# Stepper5_bakcup.net
KiCad netlist of a schematic drawn in EAGLE
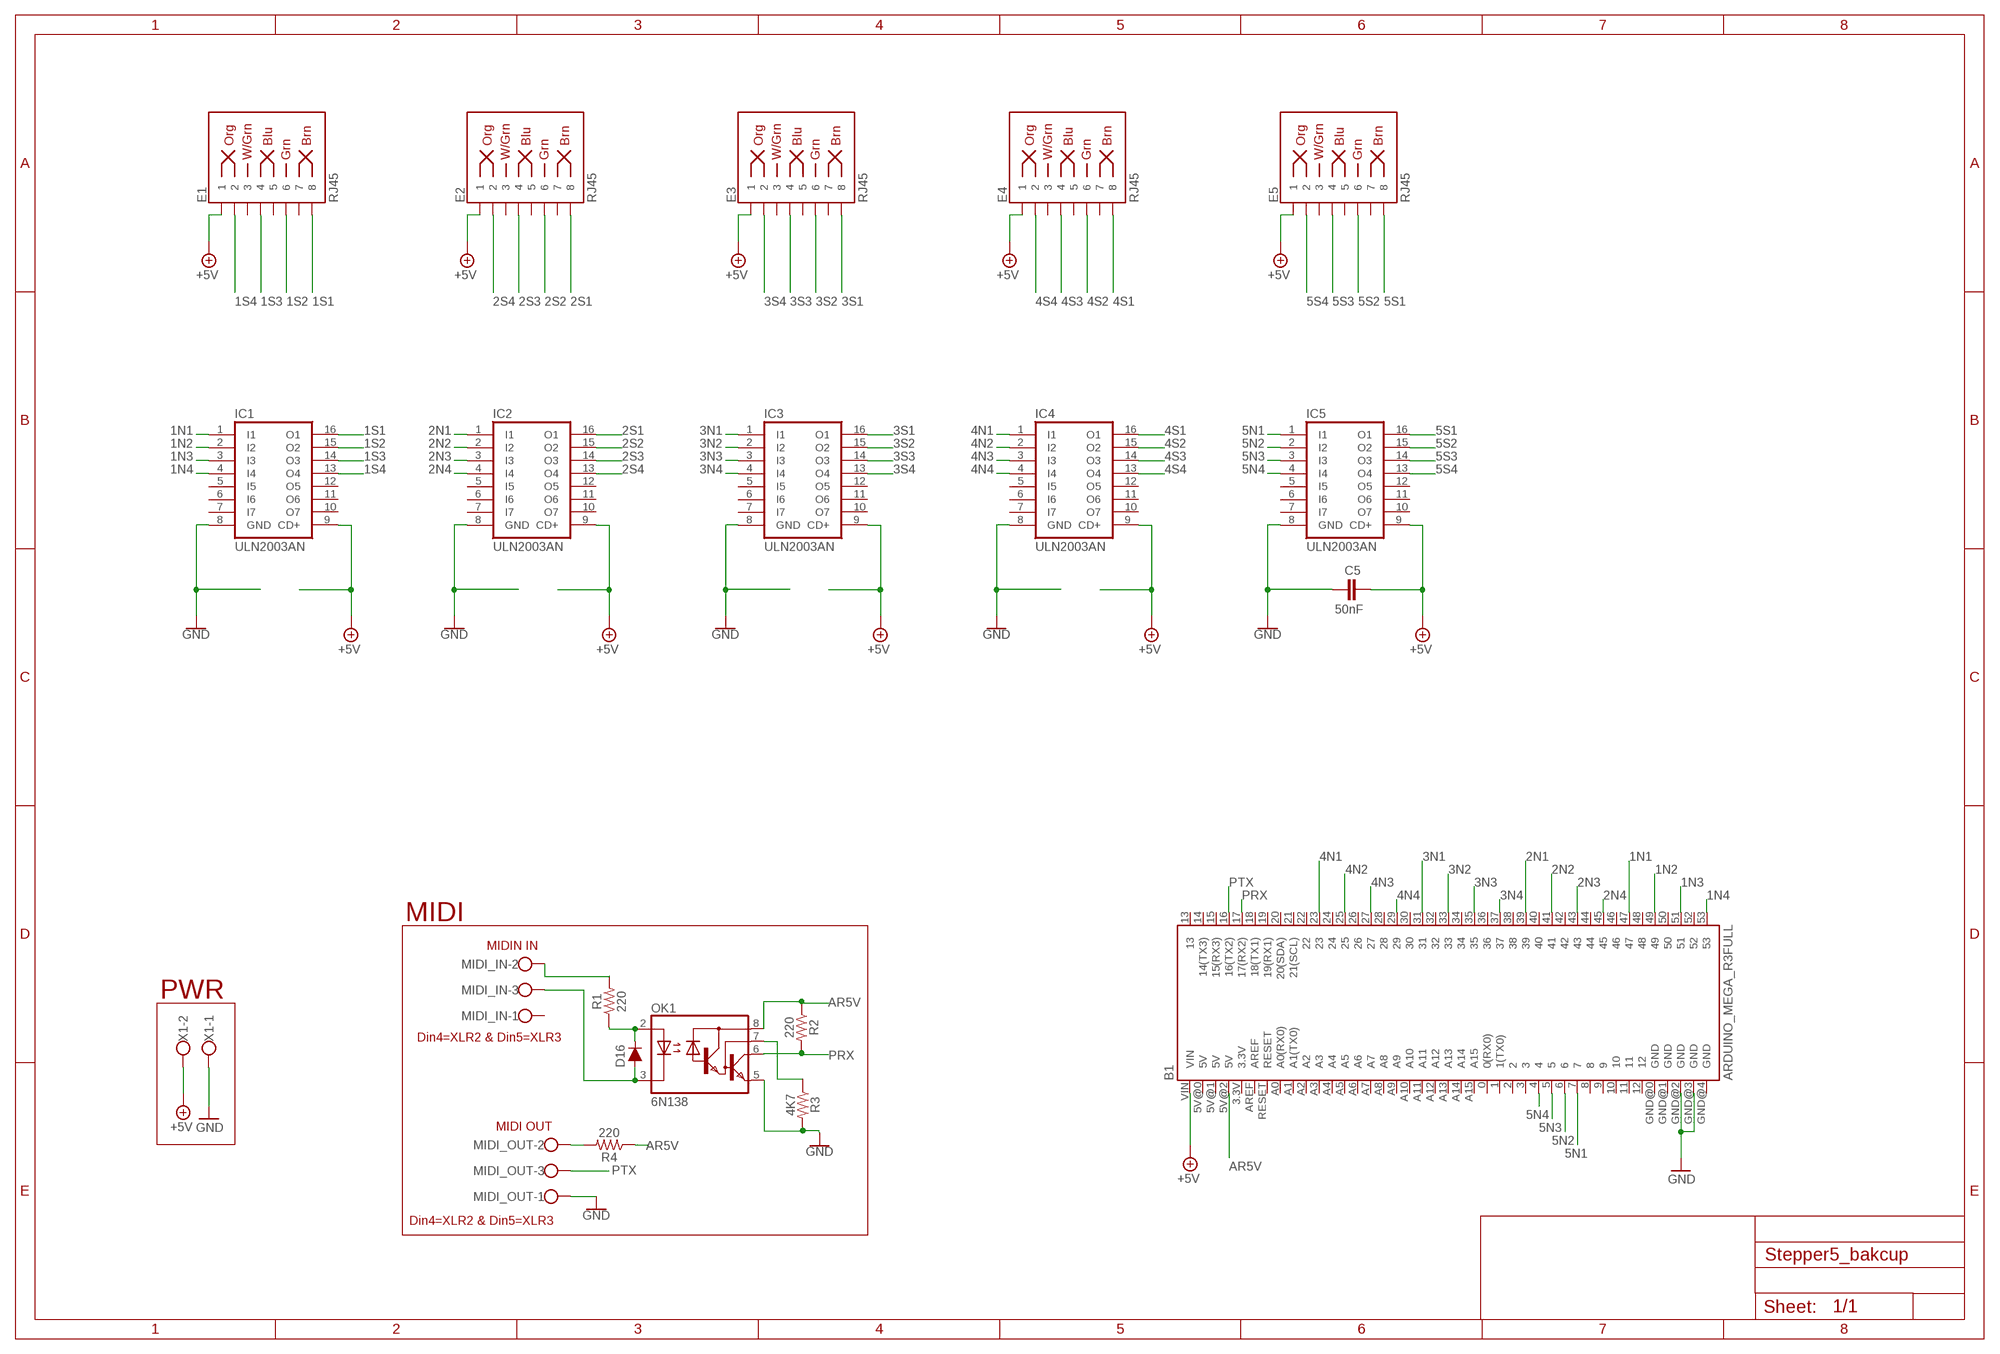
[diagram p0: schematic, sheet 1]

(export (version "E")
  (design (tool "Eeschema 10.0.6"))
  (components
    (comp (ref "B1")
      (value "ARDUINO_MEGA_R3FULL")
      (footprint "eagle-import:ARDUINO_MEGA")
      (libsource (lib "eagle-import") (part "ARDUINO_MEGA_R3FULL"))
    )
    (comp (ref "C5")
      (value "50nF")
      (footprint "eagle-import:C5B2.5")
      (libsource (lib "eagle-import") (part "C5/2.5"))
    )
    (comp (ref "D16")
      (value "200mA/100V/1V")
      (footprint "eagle-import:DIODE-1N4148")
      (libsource (lib "eagle-import") (part "DIODE-1N4148"))
    )
    (comp (ref "E1")
      (value "RJ45")
      (footprint "eagle-import:RJ45-8")
      (libsource (lib "eagle-import") (part "RJ45-8"))
    )
    (comp (ref "E2")
      (value "RJ45")
      (footprint "eagle-import:RJ45-8")
      (libsource (lib "eagle-import") (part "RJ45-8"))
    )
    (comp (ref "E3")
      (value "RJ45")
      (footprint "eagle-import:RJ45-8")
      (libsource (lib "eagle-import") (part "RJ45-8"))
    )
    (comp (ref "E4")
      (value "RJ45")
      (footprint "eagle-import:RJ45-8")
      (libsource (lib "eagle-import") (part "RJ45-8"))
    )
    (comp (ref "E5")
      (value "RJ45")
      (footprint "eagle-import:RJ45-8")
      (libsource (lib "eagle-import") (part "RJ45-8"))
    )
    (comp (ref "IC1")
      (value "ULN2003AN")
      (footprint "eagle-import:DIL16")
      (libsource (lib "eagle-import") (part "ULN2003AN"))
    )
    (comp (ref "IC2")
      (value "ULN2003AN")
      (footprint "eagle-import:DIL16")
      (libsource (lib "eagle-import") (part "ULN2003AN"))
    )
    (comp (ref "IC3")
      (value "ULN2003AN")
      (footprint "eagle-import:DIL16")
      (libsource (lib "eagle-import") (part "ULN2003AN"))
    )
    (comp (ref "IC4")
      (value "ULN2003AN")
      (footprint "eagle-import:DIL16")
      (libsource (lib "eagle-import") (part "ULN2003AN"))
    )
    (comp (ref "IC5")
      (value "ULN2003AN")
      (footprint "eagle-import:DIL16")
      (libsource (lib "eagle-import") (part "ULN2003AN"))
    )
    (comp (ref "MIDI_IN")
      (value "W237-103")
      (footprint "eagle-import:W237-103")
      (fields (field (name "MPN") "237-103"))
      (libsource (lib "eagle-import") (part "W237-103"))
    )
    (comp (ref "MIDI_OUT")
      (value "W237-103")
      (footprint "eagle-import:W237-103")
      (fields (field (name "MPN") "237-103"))
      (libsource (lib "eagle-import") (part "W237-103"))
    )
    (comp (ref "OK1")
      (value "6N138")
      (footprint "eagle-import:DIL08")
      (fields (field (name "MF") "VISHAY/TELEFUNKEN"))
      (libsource (lib "eagle-import") (part "6N138"))
    )
    (comp (ref "R1")
      (value "220")
      (footprint "eagle-import:AXIAL-0.3")
      (libsource (lib "eagle-import") (part "1KOHM-HORIZ-1/4W-5%"))
    )
    (comp (ref "R2")
      (value "220")
      (footprint "eagle-import:AXIAL-0.3")
      (libsource (lib "eagle-import") (part "1KOHM-HORIZ-1/4W-5%"))
    )
    (comp (ref "R3")
      (value "4K7")
      (footprint "eagle-import:AXIAL-0.3")
      (libsource (lib "eagle-import") (part "1KOHM-HORIZ-1/4W-5%"))
    )
    (comp (ref "R4")
      (value "220")
      (footprint "eagle-import:AXIAL-0.3")
      (libsource (lib "eagle-import") (part "1KOHM-HORIZ-1/4W-5%"))
    )
    (comp (ref "X1")
      (value "W237-102")
      (footprint "eagle-import:W237-102")
      (fields (field (name "MPN") "237-102"))
      (libsource (lib "eagle-import") (part "W237-102"))
    )
  )
  (nets
    (net (code "1") (name "+5V") (class "Default")
      (node (ref "B1") (pin "VIN") (pinfunction "VIN_VIN") (pintype "bidirectional"))
      (node (ref "C5") (pin "2") (pinfunction "2_2") (pintype "passive"))
      (node (ref "E1") (pin "1") (pinfunction "1_1") (pintype "bidirectional"))
      (node (ref "E2") (pin "1") (pinfunction "1_1") (pintype "bidirectional"))
      (node (ref "E3") (pin "1") (pinfunction "1_1") (pintype "bidirectional"))
      (node (ref "E4") (pin "1") (pinfunction "1_1") (pintype "bidirectional"))
      (node (ref "E5") (pin "1") (pinfunction "1_1") (pintype "bidirectional"))
      (node (ref "IC1") (pin "9") (pinfunction "CD+_9") (pintype "passive"))
      (node (ref "IC2") (pin "9") (pinfunction "CD+_9") (pintype "passive"))
      (node (ref "IC3") (pin "9") (pinfunction "CD+_9") (pintype "passive"))
      (node (ref "IC4") (pin "9") (pinfunction "CD+_9") (pintype "passive"))
      (node (ref "IC5") (pin "9") (pinfunction "CD+_9") (pintype "passive"))
      (node (ref "X1") (pin "2") (pinfunction "KL_2") (pintype "passive"))
    )
    (net (code "2") (name "/1N1") (class "Default")
      (node (ref "B1") (pin "47") (pinfunction "47_47") (pintype "bidirectional"))
      (node (ref "IC1") (pin "1") (pinfunction "I1_1") (pintype "input"))
    )
    (net (code "3") (name "/1N2") (class "Default")
      (node (ref "B1") (pin "49") (pinfunction "49_49") (pintype "bidirectional"))
      (node (ref "IC1") (pin "2") (pinfunction "I2_2") (pintype "input"))
    )
    (net (code "4") (name "/1N3") (class "Default")
      (node (ref "B1") (pin "51") (pinfunction "51_51") (pintype "bidirectional"))
      (node (ref "IC1") (pin "3") (pinfunction "I3_3") (pintype "input"))
    )
    (net (code "5") (name "/1N4") (class "Default")
      (node (ref "B1") (pin "53") (pinfunction "53_53") (pintype "bidirectional"))
      (node (ref "IC1") (pin "4") (pinfunction "I4_4") (pintype "input"))
    )
    (net (code "6") (name "/1S1") (class "Default")
      (node (ref "E1") (pin "8") (pinfunction "8_8") (pintype "bidirectional"))
      (node (ref "IC1") (pin "16") (pinfunction "O1_16") (pintype "open_collector"))
    )
    (net (code "7") (name "/1S2") (class "Default")
      (node (ref "E1") (pin "6") (pinfunction "6_6") (pintype "bidirectional"))
      (node (ref "IC1") (pin "15") (pinfunction "O2_15") (pintype "open_collector"))
    )
    (net (code "8") (name "/1S3") (class "Default")
      (node (ref "E1") (pin "4") (pinfunction "4_4") (pintype "bidirectional"))
      (node (ref "IC1") (pin "14") (pinfunction "O3_14") (pintype "open_collector"))
    )
    (net (code "9") (name "/1S4") (class "Default")
      (node (ref "E1") (pin "2") (pinfunction "2_2") (pintype "bidirectional"))
      (node (ref "IC1") (pin "13") (pinfunction "O4_13") (pintype "open_collector"))
    )
    (net (code "10") (name "/2N1") (class "Default")
      (node (ref "B1") (pin "39") (pinfunction "39_39") (pintype "bidirectional"))
      (node (ref "IC2") (pin "1") (pinfunction "I1_1") (pintype "input"))
    )
    (net (code "11") (name "/2N2") (class "Default")
      (node (ref "B1") (pin "41") (pinfunction "41_41") (pintype "bidirectional"))
      (node (ref "IC2") (pin "2") (pinfunction "I2_2") (pintype "input"))
    )
    (net (code "12") (name "/2N3") (class "Default")
      (node (ref "B1") (pin "43") (pinfunction "43_43") (pintype "bidirectional"))
      (node (ref "IC2") (pin "3") (pinfunction "I3_3") (pintype "input"))
    )
    (net (code "13") (name "/2N4") (class "Default")
      (node (ref "B1") (pin "45") (pinfunction "45_45") (pintype "bidirectional"))
      (node (ref "IC2") (pin "4") (pinfunction "I4_4") (pintype "input"))
    )
    (net (code "14") (name "/2S1") (class "Default")
      (node (ref "E2") (pin "8") (pinfunction "8_8") (pintype "bidirectional"))
      (node (ref "IC2") (pin "16") (pinfunction "O1_16") (pintype "open_collector"))
    )
    (net (code "15") (name "/2S2") (class "Default")
      (node (ref "E2") (pin "6") (pinfunction "6_6") (pintype "bidirectional"))
      (node (ref "IC2") (pin "15") (pinfunction "O2_15") (pintype "open_collector"))
    )
    (net (code "16") (name "/2S3") (class "Default")
      (node (ref "E2") (pin "4") (pinfunction "4_4") (pintype "bidirectional"))
      (node (ref "IC2") (pin "14") (pinfunction "O3_14") (pintype "open_collector"))
    )
    (net (code "17") (name "/2S4") (class "Default")
      (node (ref "E2") (pin "2") (pinfunction "2_2") (pintype "bidirectional"))
      (node (ref "IC2") (pin "13") (pinfunction "O4_13") (pintype "open_collector"))
    )
    (net (code "18") (name "/3N1") (class "Default")
      (node (ref "B1") (pin "31") (pinfunction "31_31") (pintype "bidirectional"))
      (node (ref "IC3") (pin "1") (pinfunction "I1_1") (pintype "input"))
    )
    (net (code "19") (name "/3N2") (class "Default")
      (node (ref "B1") (pin "33") (pinfunction "33_33") (pintype "bidirectional"))
      (node (ref "IC3") (pin "2") (pinfunction "I2_2") (pintype "input"))
    )
    (net (code "20") (name "/3N3") (class "Default")
      (node (ref "B1") (pin "35") (pinfunction "35_35") (pintype "bidirectional"))
      (node (ref "IC3") (pin "3") (pinfunction "I3_3") (pintype "input"))
    )
    (net (code "21") (name "/3N4") (class "Default")
      (node (ref "B1") (pin "37") (pinfunction "37_37") (pintype "bidirectional"))
      (node (ref "IC3") (pin "4") (pinfunction "I4_4") (pintype "input"))
    )
    (net (code "22") (name "/3S1") (class "Default")
      (node (ref "E3") (pin "8") (pinfunction "8_8") (pintype "bidirectional"))
      (node (ref "IC3") (pin "16") (pinfunction "O1_16") (pintype "open_collector"))
    )
    (net (code "23") (name "/3S2") (class "Default")
      (node (ref "E3") (pin "6") (pinfunction "6_6") (pintype "bidirectional"))
      (node (ref "IC3") (pin "15") (pinfunction "O2_15") (pintype "open_collector"))
    )
    (net (code "24") (name "/3S3") (class "Default")
      (node (ref "E3") (pin "4") (pinfunction "4_4") (pintype "bidirectional"))
      (node (ref "IC3") (pin "14") (pinfunction "O3_14") (pintype "open_collector"))
    )
    (net (code "25") (name "/3S4") (class "Default")
      (node (ref "E3") (pin "2") (pinfunction "2_2") (pintype "bidirectional"))
      (node (ref "IC3") (pin "13") (pinfunction "O4_13") (pintype "open_collector"))
    )
    (net (code "26") (name "/4N1") (class "Default")
      (node (ref "B1") (pin "23") (pinfunction "23_23") (pintype "bidirectional"))
      (node (ref "IC4") (pin "1") (pinfunction "I1_1") (pintype "input"))
    )
    (net (code "27") (name "/4N2") (class "Default")
      (node (ref "B1") (pin "25") (pinfunction "25_25") (pintype "bidirectional"))
      (node (ref "IC4") (pin "2") (pinfunction "I2_2") (pintype "input"))
    )
    (net (code "28") (name "/4N3") (class "Default")
      (node (ref "B1") (pin "27") (pinfunction "27_27") (pintype "bidirectional"))
      (node (ref "IC4") (pin "3") (pinfunction "I3_3") (pintype "input"))
    )
    (net (code "29") (name "/4N4") (class "Default")
      (node (ref "B1") (pin "29") (pinfunction "29_29") (pintype "bidirectional"))
      (node (ref "IC4") (pin "4") (pinfunction "I4_4") (pintype "input"))
    )
    (net (code "30") (name "/4S1") (class "Default")
      (node (ref "E4") (pin "8") (pinfunction "8_8") (pintype "bidirectional"))
      (node (ref "IC4") (pin "16") (pinfunction "O1_16") (pintype "open_collector"))
    )
    (net (code "31") (name "/4S2") (class "Default")
      (node (ref "E4") (pin "6") (pinfunction "6_6") (pintype "bidirectional"))
      (node (ref "IC4") (pin "15") (pinfunction "O2_15") (pintype "open_collector"))
    )
    (net (code "32") (name "/4S3") (class "Default")
      (node (ref "E4") (pin "4") (pinfunction "4_4") (pintype "bidirectional"))
      (node (ref "IC4") (pin "14") (pinfunction "O3_14") (pintype "open_collector"))
    )
    (net (code "33") (name "/4S4") (class "Default")
      (node (ref "E4") (pin "2") (pinfunction "2_2") (pintype "bidirectional"))
      (node (ref "IC4") (pin "13") (pinfunction "O4_13") (pintype "open_collector"))
    )
    (net (code "34") (name "/5N1") (class "Default")
      (node (ref "B1") (pin "7") (pinfunction "7_7") (pintype "bidirectional"))
      (node (ref "IC5") (pin "1") (pinfunction "I1_1") (pintype "input"))
    )
    (net (code "35") (name "/5N2") (class "Default")
      (node (ref "B1") (pin "6") (pinfunction "6_6") (pintype "bidirectional"))
      (node (ref "IC5") (pin "2") (pinfunction "I2_2") (pintype "input"))
    )
    (net (code "36") (name "/5N3") (class "Default")
      (node (ref "B1") (pin "5") (pinfunction "5_5") (pintype "bidirectional"))
      (node (ref "IC5") (pin "3") (pinfunction "I3_3") (pintype "input"))
    )
    (net (code "37") (name "/5N4") (class "Default")
      (node (ref "B1") (pin "4") (pinfunction "4_4") (pintype "bidirectional"))
      (node (ref "IC5") (pin "4") (pinfunction "I4_4") (pintype "input"))
    )
    (net (code "38") (name "/5S1") (class "Default")
      (node (ref "E5") (pin "8") (pinfunction "8_8") (pintype "bidirectional"))
      (node (ref "IC5") (pin "16") (pinfunction "O1_16") (pintype "open_collector"))
    )
    (net (code "39") (name "/5S2") (class "Default")
      (node (ref "E5") (pin "6") (pinfunction "6_6") (pintype "bidirectional"))
      (node (ref "IC5") (pin "15") (pinfunction "O2_15") (pintype "open_collector"))
    )
    (net (code "40") (name "/5S3") (class "Default")
      (node (ref "E5") (pin "4") (pinfunction "4_4") (pintype "bidirectional"))
      (node (ref "IC5") (pin "14") (pinfunction "O3_14") (pintype "open_collector"))
    )
    (net (code "41") (name "/5S4") (class "Default")
      (node (ref "E5") (pin "2") (pinfunction "2_2") (pintype "bidirectional"))
      (node (ref "IC5") (pin "13") (pinfunction "O4_13") (pintype "open_collector"))
    )
    (net (code "42") (name "/AR5V") (class "Default")
      (node (ref "B1") (pin "5V@2") (pinfunction "5V_5V@2") (pintype "bidirectional"))
      (node (ref "OK1") (pin "8") (pinfunction "VCC_8") (pintype "passive"))
      (node (ref "R2") (pin "P$1") (pinfunction "1_P$1") (pintype "passive"))
      (node (ref "R4") (pin "P$1") (pinfunction "1_P$1") (pintype "passive"))
    )
    (net (code "43") (name "/PRX") (class "Default")
      (node (ref "B1") (pin "17") (pinfunction "17(RX2)_17") (pintype "bidirectional"))
      (node (ref "OK1") (pin "6") (pinfunction "VO_6") (pintype "passive"))
      (node (ref "R2") (pin "P$2") (pinfunction "2_P$2") (pintype "passive"))
    )
    (net (code "44") (name "/PTX") (class "Default")
      (node (ref "B1") (pin "16") (pinfunction "16(TX2)_16") (pintype "bidirectional"))
      (node (ref "MIDI_OUT") (pin "3") (pinfunction "KL_3") (pintype "passive"))
    )
    (net (code "45") (name "GND") (class "Default")
      (node (ref "B1") (pin "GND@2") (pinfunction "GND_GND@2") (pintype "bidirectional"))
      (node (ref "B1") (pin "GND@3") (pinfunction "GND_GND@3") (pintype "bidirectional"))
      (node (ref "C5") (pin "1") (pinfunction "1_1") (pintype "passive"))
      (node (ref "IC1") (pin "8") (pinfunction "GND_8") (pintype "power_in"))
      (node (ref "IC2") (pin "8") (pinfunction "GND_8") (pintype "power_in"))
      (node (ref "IC3") (pin "8") (pinfunction "GND_8") (pintype "power_in"))
      (node (ref "IC4") (pin "8") (pinfunction "GND_8") (pintype "power_in"))
      (node (ref "IC5") (pin "8") (pinfunction "GND_8") (pintype "power_in"))
      (node (ref "MIDI_OUT") (pin "1") (pinfunction "KL_1") (pintype "passive"))
      (node (ref "OK1") (pin "5") (pinfunction "GND_5") (pintype "passive"))
      (node (ref "R3") (pin "P$2") (pinfunction "2_P$2") (pintype "passive"))
      (node (ref "X1") (pin "1") (pinfunction "KL_1") (pintype "passive"))
    )
    (net (code "46") (name "Net-(MIDI_INB-KL)") (class "Default")
      (node (ref "MIDI_IN") (pin "2") (pinfunction "KL_2") (pintype "passive"))
      (node (ref "R1") (pin "P$2") (pinfunction "2_P$2") (pintype "passive"))
    )
    (net (code "47") (name "Net-(MIDI_INC-KL)") (class "Default")
      (node (ref "D16") (pin "A") (pinfunction "A_A") (pintype "passive"))
      (node (ref "MIDI_IN") (pin "3") (pinfunction "KL_3") (pintype "passive"))
      (node (ref "OK1") (pin "3") (pinfunction "C_3") (pintype "passive"))
    )
    (net (code "48") (name "Net-(MIDI_OUTB-KL)") (class "Default")
      (node (ref "MIDI_OUT") (pin "2") (pinfunction "KL_2") (pintype "passive"))
      (node (ref "R4") (pin "P$2") (pinfunction "2_P$2") (pintype "passive"))
    )
    (net (code "49") (name "Net-(OK1-A)") (class "Default")
      (node (ref "D16") (pin "C") (pinfunction "C_C") (pintype "passive"))
      (node (ref "OK1") (pin "2") (pinfunction "A_2") (pintype "passive"))
      (node (ref "R1") (pin "P$1") (pinfunction "1_P$1") (pintype "passive"))
    )
    (net (code "50") (name "Net-(OK1-VB)") (class "Default")
      (node (ref "OK1") (pin "7") (pinfunction "VB_7") (pintype "passive"))
      (node (ref "R3") (pin "P$1") (pinfunction "1_P$1") (pintype "passive"))
    )
    (net (code "51") (name "unconnected-(B1-0(RX0)-Pad0)") (class "Default")
      (node (ref "B1") (pin "0") (pinfunction "0(RX0)_0") (pintype "bidirectional"))
    )
    (net (code "52") (name "unconnected-(B1-1(TX0)-Pad1)") (class "Default")
      (node (ref "B1") (pin "1") (pinfunction "1(TX0)_1") (pintype "bidirectional"))
    )
    (net (code "53") (name "unconnected-(B1-5V-Pad5V@0)") (class "Default")
      (node (ref "B1") (pin "5V@0") (pinfunction "5V_5V@0") (pintype "bidirectional"))
    )
    (net (code "54") (name "unconnected-(B1-5V-Pad5V@1)") (class "Default")
      (node (ref "B1") (pin "5V@1") (pinfunction "5V_5V@1") (pintype "bidirectional"))
    )
    (net (code "55") (name "unconnected-(B1-14(TX3)-Pad14)") (class "Default")
      (node (ref "B1") (pin "14") (pinfunction "14(TX3)_14") (pintype "bidirectional"))
    )
    (net (code "56") (name "unconnected-(B1-15(RX3)-Pad15)") (class "Default")
      (node (ref "B1") (pin "15") (pinfunction "15(RX3)_15") (pintype "bidirectional"))
    )
    (net (code "57") (name "unconnected-(B1-18(TX1)-Pad18)") (class "Default")
      (node (ref "B1") (pin "18") (pinfunction "18(TX1)_18") (pintype "bidirectional"))
    )
    (net (code "58") (name "unconnected-(B1-19(RX1)-Pad19)") (class "Default")
      (node (ref "B1") (pin "19") (pinfunction "19(RX1)_19") (pintype "bidirectional"))
    )
    (net (code "59") (name "unconnected-(B1-20(SDA)-Pad20)") (class "Default")
      (node (ref "B1") (pin "20") (pinfunction "20(SDA)_20") (pintype "bidirectional"))
    )
    (net (code "60") (name "unconnected-(B1-21(SCL)-Pad21)") (class "Default")
      (node (ref "B1") (pin "21") (pinfunction "21(SCL)_21") (pintype "bidirectional"))
    )
    (net (code "61") (name "unconnected-(B1-A0(RX0)-PadA0)") (class "Default")
      (node (ref "B1") (pin "A0") (pinfunction "A0(RX0)_A0") (pintype "bidirectional"))
    )
    (net (code "62") (name "unconnected-(B1-A1(TX0)-PadA1)") (class "Default")
      (node (ref "B1") (pin "A1") (pinfunction "A1(TX0)_A1") (pintype "bidirectional"))
    )
    (net (code "63") (name "unconnected-(B1-GND-PadGND@0)") (class "Default")
      (node (ref "B1") (pin "GND@0") (pinfunction "GND_GND@0") (pintype "bidirectional"))
    )
    (net (code "64") (name "unconnected-(B1-GND-PadGND@1)") (class "Default")
      (node (ref "B1") (pin "GND@1") (pinfunction "GND_GND@1") (pintype "bidirectional"))
    )
    (net (code "65") (name "unconnected-(B1-GND-PadGND@4)") (class "Default")
      (node (ref "B1") (pin "GND@4") (pinfunction "GND_GND@4") (pintype "bidirectional"))
    )
    (net (code "66") (name "unconnected-(B1-Pad2)") (class "Default")
      (node (ref "B1") (pin "2") (pinfunction "2_2") (pintype "bidirectional"))
    )
    (net (code "67") (name "unconnected-(B1-Pad3)") (class "Default")
      (node (ref "B1") (pin "3") (pinfunction "3_3") (pintype "bidirectional"))
    )
    (net (code "68") (name "unconnected-(B1-Pad3.3V)") (class "Default")
      (node (ref "B1") (pin "3.3V") (pinfunction "3.3V_3.3V") (pintype "bidirectional"))
    )
    (net (code "69") (name "unconnected-(B1-Pad8)") (class "Default")
      (node (ref "B1") (pin "8") (pinfunction "8_8") (pintype "bidirectional"))
    )
    (net (code "70") (name "unconnected-(B1-Pad9)") (class "Default")
      (node (ref "B1") (pin "9") (pinfunction "9_9") (pintype "bidirectional"))
    )
    (net (code "71") (name "unconnected-(B1-Pad10)") (class "Default")
      (node (ref "B1") (pin "10") (pinfunction "10_10") (pintype "bidirectional"))
    )
    (net (code "72") (name "unconnected-(B1-Pad11)") (class "Default")
      (node (ref "B1") (pin "11") (pinfunction "11_11") (pintype "bidirectional"))
    )
    (net (code "73") (name "unconnected-(B1-Pad12)") (class "Default")
      (node (ref "B1") (pin "12") (pinfunction "12_12") (pintype "bidirectional"))
    )
    (net (code "74") (name "unconnected-(B1-Pad13)") (class "Default")
      (node (ref "B1") (pin "13") (pinfunction "13_13") (pintype "bidirectional"))
    )
    (net (code "75") (name "unconnected-(B1-Pad22)") (class "Default")
      (node (ref "B1") (pin "22") (pinfunction "22_22") (pintype "bidirectional"))
    )
    (net (code "76") (name "unconnected-(B1-Pad24)") (class "Default")
      (node (ref "B1") (pin "24") (pinfunction "24_24") (pintype "bidirectional"))
    )
    (net (code "77") (name "unconnected-(B1-Pad26)") (class "Default")
      (node (ref "B1") (pin "26") (pinfunction "26_26") (pintype "bidirectional"))
    )
    (net (code "78") (name "unconnected-(B1-Pad28)") (class "Default")
      (node (ref "B1") (pin "28") (pinfunction "28_28") (pintype "bidirectional"))
    )
    (net (code "79") (name "unconnected-(B1-Pad30)") (class "Default")
      (node (ref "B1") (pin "30") (pinfunction "30_30") (pintype "bidirectional"))
    )
    (net (code "80") (name "unconnected-(B1-Pad32)") (class "Default")
      (node (ref "B1") (pin "32") (pinfunction "32_32") (pintype "bidirectional"))
    )
    (net (code "81") (name "unconnected-(B1-Pad34)") (class "Default")
      (node (ref "B1") (pin "34") (pinfunction "34_34") (pintype "bidirectional"))
    )
    (net (code "82") (name "unconnected-(B1-Pad36)") (class "Default")
      (node (ref "B1") (pin "36") (pinfunction "36_36") (pintype "bidirectional"))
    )
    (net (code "83") (name "unconnected-(B1-Pad38)") (class "Default")
      (node (ref "B1") (pin "38") (pinfunction "38_38") (pintype "bidirectional"))
    )
    (net (code "84") (name "unconnected-(B1-Pad40)") (class "Default")
      (node (ref "B1") (pin "40") (pinfunction "40_40") (pintype "bidirectional"))
    )
    (net (code "85") (name "unconnected-(B1-Pad42)") (class "Default")
      (node (ref "B1") (pin "42") (pinfunction "42_42") (pintype "bidirectional"))
    )
    (net (code "86") (name "unconnected-(B1-Pad44)") (class "Default")
      (node (ref "B1") (pin "44") (pinfunction "44_44") (pintype "bidirectional"))
    )
    (net (code "87") (name "unconnected-(B1-Pad46)") (class "Default")
      (node (ref "B1") (pin "46") (pinfunction "46_46") (pintype "bidirectional"))
    )
    (net (code "88") (name "unconnected-(B1-Pad48)") (class "Default")
      (node (ref "B1") (pin "48") (pinfunction "48_48") (pintype "bidirectional"))
    )
    (net (code "89") (name "unconnected-(B1-Pad50)") (class "Default")
      (node (ref "B1") (pin "50") (pinfunction "50_50") (pintype "bidirectional"))
    )
    (net (code "90") (name "unconnected-(B1-Pad52)") (class "Default")
      (node (ref "B1") (pin "52") (pinfunction "52_52") (pintype "bidirectional"))
    )
    (net (code "91") (name "unconnected-(B1-PadA2)") (class "Default")
      (node (ref "B1") (pin "A2") (pinfunction "A2_A2") (pintype "bidirectional"))
    )
    (net (code "92") (name "unconnected-(B1-PadA3)") (class "Default")
      (node (ref "B1") (pin "A3") (pinfunction "A3_A3") (pintype "bidirectional"))
    )
    (net (code "93") (name "unconnected-(B1-PadA4)") (class "Default")
      (node (ref "B1") (pin "A4") (pinfunction "A4_A4") (pintype "bidirectional"))
    )
    (net (code "94") (name "unconnected-(B1-PadA5)") (class "Default")
      (node (ref "B1") (pin "A5") (pinfunction "A5_A5") (pintype "bidirectional"))
    )
    (net (code "95") (name "unconnected-(B1-PadA6)") (class "Default")
      (node (ref "B1") (pin "A6") (pinfunction "A6_A6") (pintype "bidirectional"))
    )
    (net (code "96") (name "unconnected-(B1-PadA7)") (class "Default")
      (node (ref "B1") (pin "A7") (pinfunction "A7_A7") (pintype "bidirectional"))
    )
    (net (code "97") (name "unconnected-(B1-PadA8)") (class "Default")
      (node (ref "B1") (pin "A8") (pinfunction "A8_A8") (pintype "bidirectional"))
    )
    (net (code "98") (name "unconnected-(B1-PadA9)") (class "Default")
      (node (ref "B1") (pin "A9") (pinfunction "A9_A9") (pintype "bidirectional"))
    )
    (net (code "99") (name "unconnected-(B1-PadA10)") (class "Default")
      (node (ref "B1") (pin "A10") (pinfunction "A10_A10") (pintype "bidirectional"))
    )
    (net (code "100") (name "unconnected-(B1-PadA11)") (class "Default")
      (node (ref "B1") (pin "A11") (pinfunction "A11_A11") (pintype "bidirectional"))
    )
    (net (code "101") (name "unconnected-(B1-PadA12)") (class "Default")
      (node (ref "B1") (pin "A12") (pinfunction "A12_A12") (pintype "bidirectional"))
    )
    (net (code "102") (name "unconnected-(B1-PadA13)") (class "Default")
      (node (ref "B1") (pin "A13") (pinfunction "A13_A13") (pintype "bidirectional"))
    )
    (net (code "103") (name "unconnected-(B1-PadA14)") (class "Default")
      (node (ref "B1") (pin "A14") (pinfunction "A14_A14") (pintype "bidirectional"))
    )
    (net (code "104") (name "unconnected-(B1-PadA15)") (class "Default")
      (node (ref "B1") (pin "A15") (pinfunction "A15_A15") (pintype "bidirectional"))
    )
    (net (code "105") (name "unconnected-(B1-PadAREF)") (class "Default")
      (node (ref "B1") (pin "AREF") (pinfunction "AREF_AREF") (pintype "bidirectional"))
    )
    (net (code "106") (name "unconnected-(B1-PadRESET)") (class "Default")
      (node (ref "B1") (pin "RESET") (pinfunction "RESET_RESET") (pintype "bidirectional"))
    )
    (net (code "107") (name "unconnected-(E1-Pad3)") (class "Default")
      (node (ref "E1") (pin "3") (pinfunction "3_3") (pintype "bidirectional"))
    )
    (net (code "108") (name "unconnected-(E1-Pad5)") (class "Default")
      (node (ref "E1") (pin "5") (pinfunction "5_5") (pintype "bidirectional"))
    )
    (net (code "109") (name "unconnected-(E1-Pad7)") (class "Default")
      (node (ref "E1") (pin "7") (pinfunction "7_7") (pintype "bidirectional"))
    )
    (net (code "110") (name "unconnected-(E2-Pad3)") (class "Default")
      (node (ref "E2") (pin "3") (pinfunction "3_3") (pintype "bidirectional"))
    )
    (net (code "111") (name "unconnected-(E2-Pad5)") (class "Default")
      (node (ref "E2") (pin "5") (pinfunction "5_5") (pintype "bidirectional"))
    )
    (net (code "112") (name "unconnected-(E2-Pad7)") (class "Default")
      (node (ref "E2") (pin "7") (pinfunction "7_7") (pintype "bidirectional"))
    )
    (net (code "113") (name "unconnected-(E3-Pad3)") (class "Default")
      (node (ref "E3") (pin "3") (pinfunction "3_3") (pintype "bidirectional"))
    )
    (net (code "114") (name "unconnected-(E3-Pad5)") (class "Default")
      (node (ref "E3") (pin "5") (pinfunction "5_5") (pintype "bidirectional"))
    )
    (net (code "115") (name "unconnected-(E3-Pad7)") (class "Default")
      (node (ref "E3") (pin "7") (pinfunction "7_7") (pintype "bidirectional"))
    )
    (net (code "116") (name "unconnected-(E4-Pad3)") (class "Default")
      (node (ref "E4") (pin "3") (pinfunction "3_3") (pintype "bidirectional"))
    )
    (net (code "117") (name "unconnected-(E4-Pad5)") (class "Default")
      (node (ref "E4") (pin "5") (pinfunction "5_5") (pintype "bidirectional"))
    )
    (net (code "118") (name "unconnected-(E4-Pad7)") (class "Default")
      (node (ref "E4") (pin "7") (pinfunction "7_7") (pintype "bidirectional"))
    )
    (net (code "119") (name "unconnected-(E5-Pad3)") (class "Default")
      (node (ref "E5") (pin "3") (pinfunction "3_3") (pintype "bidirectional"))
    )
    (net (code "120") (name "unconnected-(E5-Pad5)") (class "Default")
      (node (ref "E5") (pin "5") (pinfunction "5_5") (pintype "bidirectional"))
    )
    (net (code "121") (name "unconnected-(E5-Pad7)") (class "Default")
      (node (ref "E5") (pin "7") (pinfunction "7_7") (pintype "bidirectional"))
    )
    (net (code "122") (name "unconnected-(IC1-I5-Pad5)") (class "Default")
      (node (ref "IC1") (pin "5") (pinfunction "I5_5") (pintype "input"))
    )
    (net (code "123") (name "unconnected-(IC1-I6-Pad6)") (class "Default")
      (node (ref "IC1") (pin "6") (pinfunction "I6_6") (pintype "input"))
    )
    (net (code "124") (name "unconnected-(IC1-I7-Pad7)") (class "Default")
      (node (ref "IC1") (pin "7") (pinfunction "I7_7") (pintype "input"))
    )
    (net (code "125") (name "unconnected-(IC1-O5-Pad12)") (class "Default")
      (node (ref "IC1") (pin "12") (pinfunction "O5_12") (pintype "open_collector"))
    )
    (net (code "126") (name "unconnected-(IC1-O6-Pad11)") (class "Default")
      (node (ref "IC1") (pin "11") (pinfunction "O6_11") (pintype "open_collector"))
    )
    (net (code "127") (name "unconnected-(IC1-O7-Pad10)") (class "Default")
      (node (ref "IC1") (pin "10") (pinfunction "O7_10") (pintype "open_collector"))
    )
    (net (code "128") (name "unconnected-(IC2-I5-Pad5)") (class "Default")
      (node (ref "IC2") (pin "5") (pinfunction "I5_5") (pintype "input"))
    )
    (net (code "129") (name "unconnected-(IC2-I6-Pad6)") (class "Default")
      (node (ref "IC2") (pin "6") (pinfunction "I6_6") (pintype "input"))
    )
    (net (code "130") (name "unconnected-(IC2-I7-Pad7)") (class "Default")
      (node (ref "IC2") (pin "7") (pinfunction "I7_7") (pintype "input"))
    )
    (net (code "131") (name "unconnected-(IC2-O5-Pad12)") (class "Default")
      (node (ref "IC2") (pin "12") (pinfunction "O5_12") (pintype "open_collector"))
    )
    (net (code "132") (name "unconnected-(IC2-O6-Pad11)") (class "Default")
      (node (ref "IC2") (pin "11") (pinfunction "O6_11") (pintype "open_collector"))
    )
    (net (code "133") (name "unconnected-(IC2-O7-Pad10)") (class "Default")
      (node (ref "IC2") (pin "10") (pinfunction "O7_10") (pintype "open_collector"))
    )
    (net (code "134") (name "unconnected-(IC3-I5-Pad5)") (class "Default")
      (node (ref "IC3") (pin "5") (pinfunction "I5_5") (pintype "input"))
    )
    (net (code "135") (name "unconnected-(IC3-I6-Pad6)") (class "Default")
      (node (ref "IC3") (pin "6") (pinfunction "I6_6") (pintype "input"))
    )
    (net (code "136") (name "unconnected-(IC3-I7-Pad7)") (class "Default")
      (node (ref "IC3") (pin "7") (pinfunction "I7_7") (pintype "input"))
    )
    (net (code "137") (name "unconnected-(IC3-O5-Pad12)") (class "Default")
      (node (ref "IC3") (pin "12") (pinfunction "O5_12") (pintype "open_collector"))
    )
    (net (code "138") (name "unconnected-(IC3-O6-Pad11)") (class "Default")
      (node (ref "IC3") (pin "11") (pinfunction "O6_11") (pintype "open_collector"))
    )
    (net (code "139") (name "unconnected-(IC3-O7-Pad10)") (class "Default")
      (node (ref "IC3") (pin "10") (pinfunction "O7_10") (pintype "open_collector"))
    )
    (net (code "140") (name "unconnected-(IC4-I5-Pad5)") (class "Default")
      (node (ref "IC4") (pin "5") (pinfunction "I5_5") (pintype "input"))
    )
    (net (code "141") (name "unconnected-(IC4-I6-Pad6)") (class "Default")
      (node (ref "IC4") (pin "6") (pinfunction "I6_6") (pintype "input"))
    )
    (net (code "142") (name "unconnected-(IC4-I7-Pad7)") (class "Default")
      (node (ref "IC4") (pin "7") (pinfunction "I7_7") (pintype "input"))
    )
    (net (code "143") (name "unconnected-(IC4-O5-Pad12)") (class "Default")
      (node (ref "IC4") (pin "12") (pinfunction "O5_12") (pintype "open_collector"))
    )
    (net (code "144") (name "unconnected-(IC4-O6-Pad11)") (class "Default")
      (node (ref "IC4") (pin "11") (pinfunction "O6_11") (pintype "open_collector"))
    )
    (net (code "145") (name "unconnected-(IC4-O7-Pad10)") (class "Default")
      (node (ref "IC4") (pin "10") (pinfunction "O7_10") (pintype "open_collector"))
    )
    (net (code "146") (name "unconnected-(IC5-I5-Pad5)") (class "Default")
      (node (ref "IC5") (pin "5") (pinfunction "I5_5") (pintype "input"))
    )
    (net (code "147") (name "unconnected-(IC5-I6-Pad6)") (class "Default")
      (node (ref "IC5") (pin "6") (pinfunction "I6_6") (pintype "input"))
    )
    (net (code "148") (name "unconnected-(IC5-I7-Pad7)") (class "Default")
      (node (ref "IC5") (pin "7") (pinfunction "I7_7") (pintype "input"))
    )
    (net (code "149") (name "unconnected-(IC5-O5-Pad12)") (class "Default")
      (node (ref "IC5") (pin "12") (pinfunction "O5_12") (pintype "open_collector"))
    )
    (net (code "150") (name "unconnected-(IC5-O6-Pad11)") (class "Default")
      (node (ref "IC5") (pin "11") (pinfunction "O6_11") (pintype "open_collector"))
    )
    (net (code "151") (name "unconnected-(IC5-O7-Pad10)") (class "Default")
      (node (ref "IC5") (pin "10") (pinfunction "O7_10") (pintype "open_collector"))
    )
    (net (code "152") (name "unconnected-(MIDI_INA-KL-Pad1)") (class "Default")
      (node (ref "MIDI_IN") (pin "1") (pinfunction "KL_1") (pintype "passive"))
    )
  )
)
